# TOP.net
KiCad netlist of a schematic drawn in Altium Designer
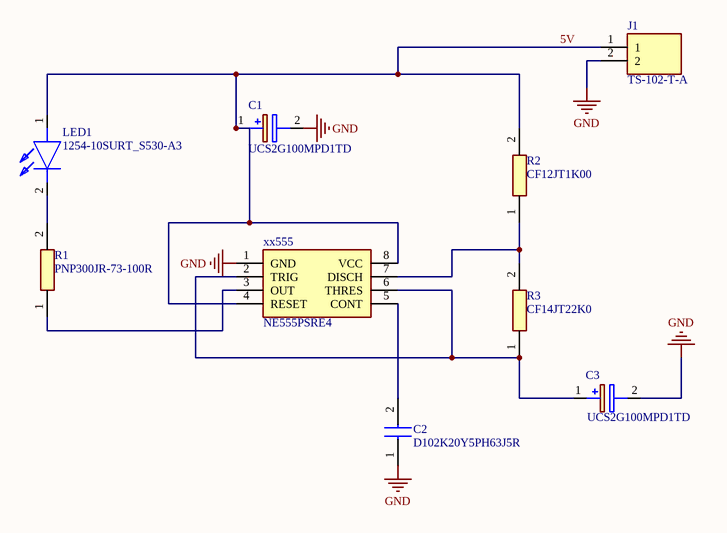
[diagram p0: TOP.SchDoc]

(export (version "E")
  (design (tool "Eeschema 10.0.6"))
  (components
    (comp (ref "C1")
      (value "UCS2G100MPD1TD")
      (footprint "SamacSys:CAPPRD500W60D1025H2150")
      (description "Capacitor Polarised")
      (fields (field (name "MOUSER PART NUMBER") "647-UCS2G100MPD1TD"))
      (libsource (lib "*") (part "UCS2G100MPD1TD"))
    )
    (comp (ref "C2")
      (value "D102K20Y5PH63J5R")
      (footprint "SamacSys:D102K20Y5PH63J5R")
      (description "Capacitor")
      (fields (field (name "MOUSER PART NUMBER") "594-D102K20Y5PH63J5R"))
      (libsource (lib "*") (part "D102K20Y5PH63J5R"))
    )
    (comp (ref "C3")
      (value "UCS2G100MPD1TD")
      (footprint "SamacSys:CAPPRD500W60D1025H2150")
      (description "Capacitor Polarised")
      (fields (field (name "MOUSER PART NUMBER") "647-UCS2G100MPD1TD"))
      (libsource (lib "*") (part "UCS2G100MPD1TD"))
    )
    (comp (ref "J1")
      (value "TS-102-T-A")
      (footprint "SamacSys:SAMTEC_TS-102-T-A")
      (description "Connector")
      (fields (field (name "MOUSER PART NUMBER") "200-TS102TA"))
      (libsource (lib "*") (part "TS-102-T-A"))
    )
    (comp (ref "LED1")
      (value "1254-10SURT_S530-A3")
      (footprint "SamacSys:125410SURTS530A3")
      (description "LED")
      (fields (field (name "MANUFACTURER_PART_NUMBER") "1254-10SURT/S530-A3"))
      (libsource (lib "*") (part "1254-10SURT_S530-A3"))
    )
    (comp (ref "R1")
      (value "PNP300JR-73-100R")
      (footprint "SamacSys:RESAD2990W85L1150D460")
      (description "Resistor")
      (fields (field (name "MOUSER PART NUMBER") "603-PNP300JR-73-100R"))
      (libsource (lib "*") (part "PNP300JR-73-100R"))
    )
    (comp (ref "R2")
      (value "CF12JT1K00")
      (footprint "SamacSys:RESAD1930W63L850D270")
      (description "Resistor")
      (fields (field (name "MOUSER PART NUMBER") "708-CF12JT1K00"))
      (libsource (lib "*") (part "CF12JT1K00"))
    )
    (comp (ref "R3")
      (value "CF14JT22K0")
      (footprint "SamacSys:RESAD1520W63L600D230")
      (description "Resistor")
      (libsource (lib "*") (part "CF14JT22K0"))
    )
    (comp (ref "xx555")
      (value "NE555PSRE4")
      (footprint "SamacSys:SOIC127P780X200-8N")
      (description "Integrated Circuit")
      (fields (field (name "MOUSER PART NUMBER") "595-NE555PSRE4"))
      (libsource (lib "*") (part "NE555PSRE4"))
    )
  )
  (nets
    (net (code "1") (name "/5V") (class "Default")
      (node (ref "C1") (pin "1") (pinfunction "+_1") (pintype "passive"))
      (node (ref "J1") (pin "1") (pinfunction "1_1") (pintype "passive"))
      (node (ref "LED1") (pin "1") (pinfunction "A_1") (pintype "passive"))
      (node (ref "R2") (pin "2") (pinfunction "2_2") (pintype "passive"))
      (node (ref "xx555") (pin "4") (pinfunction "RESET_4") (pintype "passive"))
      (node (ref "xx555") (pin "8") (pinfunction "VCC_8") (pintype "passive"))
    )
    (net (code "2") (name "GND") (class "Default")
      (node (ref "C1") (pin "2") (pinfunction "-_2") (pintype "passive"))
      (node (ref "C2") (pin "1") (pinfunction "1_1") (pintype "passive"))
      (node (ref "C3") (pin "2") (pinfunction "-_2") (pintype "passive"))
      (node (ref "J1") (pin "2") (pinfunction "2_2") (pintype "passive"))
      (node (ref "xx555") (pin "1") (pinfunction "GND_1") (pintype "passive"))
    )
    (net (code "3") (name "Net-(C3-+)") (class "Default")
      (node (ref "C3") (pin "1") (pinfunction "+_1") (pintype "passive"))
      (node (ref "R3") (pin "1") (pinfunction "1_1") (pintype "passive"))
      (node (ref "xx555") (pin "2") (pinfunction "TRIG_2") (pintype "passive"))
      (node (ref "xx555") (pin "6") (pinfunction "THRES_6") (pintype "passive"))
    )
    (net (code "4") (name "Net-(LED1-K)") (class "Default")
      (node (ref "LED1") (pin "2") (pinfunction "K_2") (pintype "passive"))
      (node (ref "R1") (pin "2") (pinfunction "2_2") (pintype "passive"))
    )
    (net (code "5") (name "Net-(xx555-CONT)") (class "Default")
      (node (ref "C2") (pin "2") (pinfunction "2_2") (pintype "passive"))
      (node (ref "xx555") (pin "5") (pinfunction "CONT_5") (pintype "passive"))
    )
    (net (code "6") (name "Net-(xx555-DISCH)") (class "Default")
      (node (ref "R2") (pin "1") (pinfunction "1_1") (pintype "passive"))
      (node (ref "R3") (pin "2") (pinfunction "2_2") (pintype "passive"))
      (node (ref "xx555") (pin "7") (pinfunction "DISCH_7") (pintype "passive"))
    )
    (net (code "7") (name "Net-(xx555-OUT)") (class "Default")
      (node (ref "R1") (pin "1") (pinfunction "1_1") (pintype "passive"))
      (node (ref "xx555") (pin "3") (pinfunction "OUT_3") (pintype "passive"))
    )
  )
)
